# V1_9.net
KiCad netlist of a schematic drawn in Altium Designer
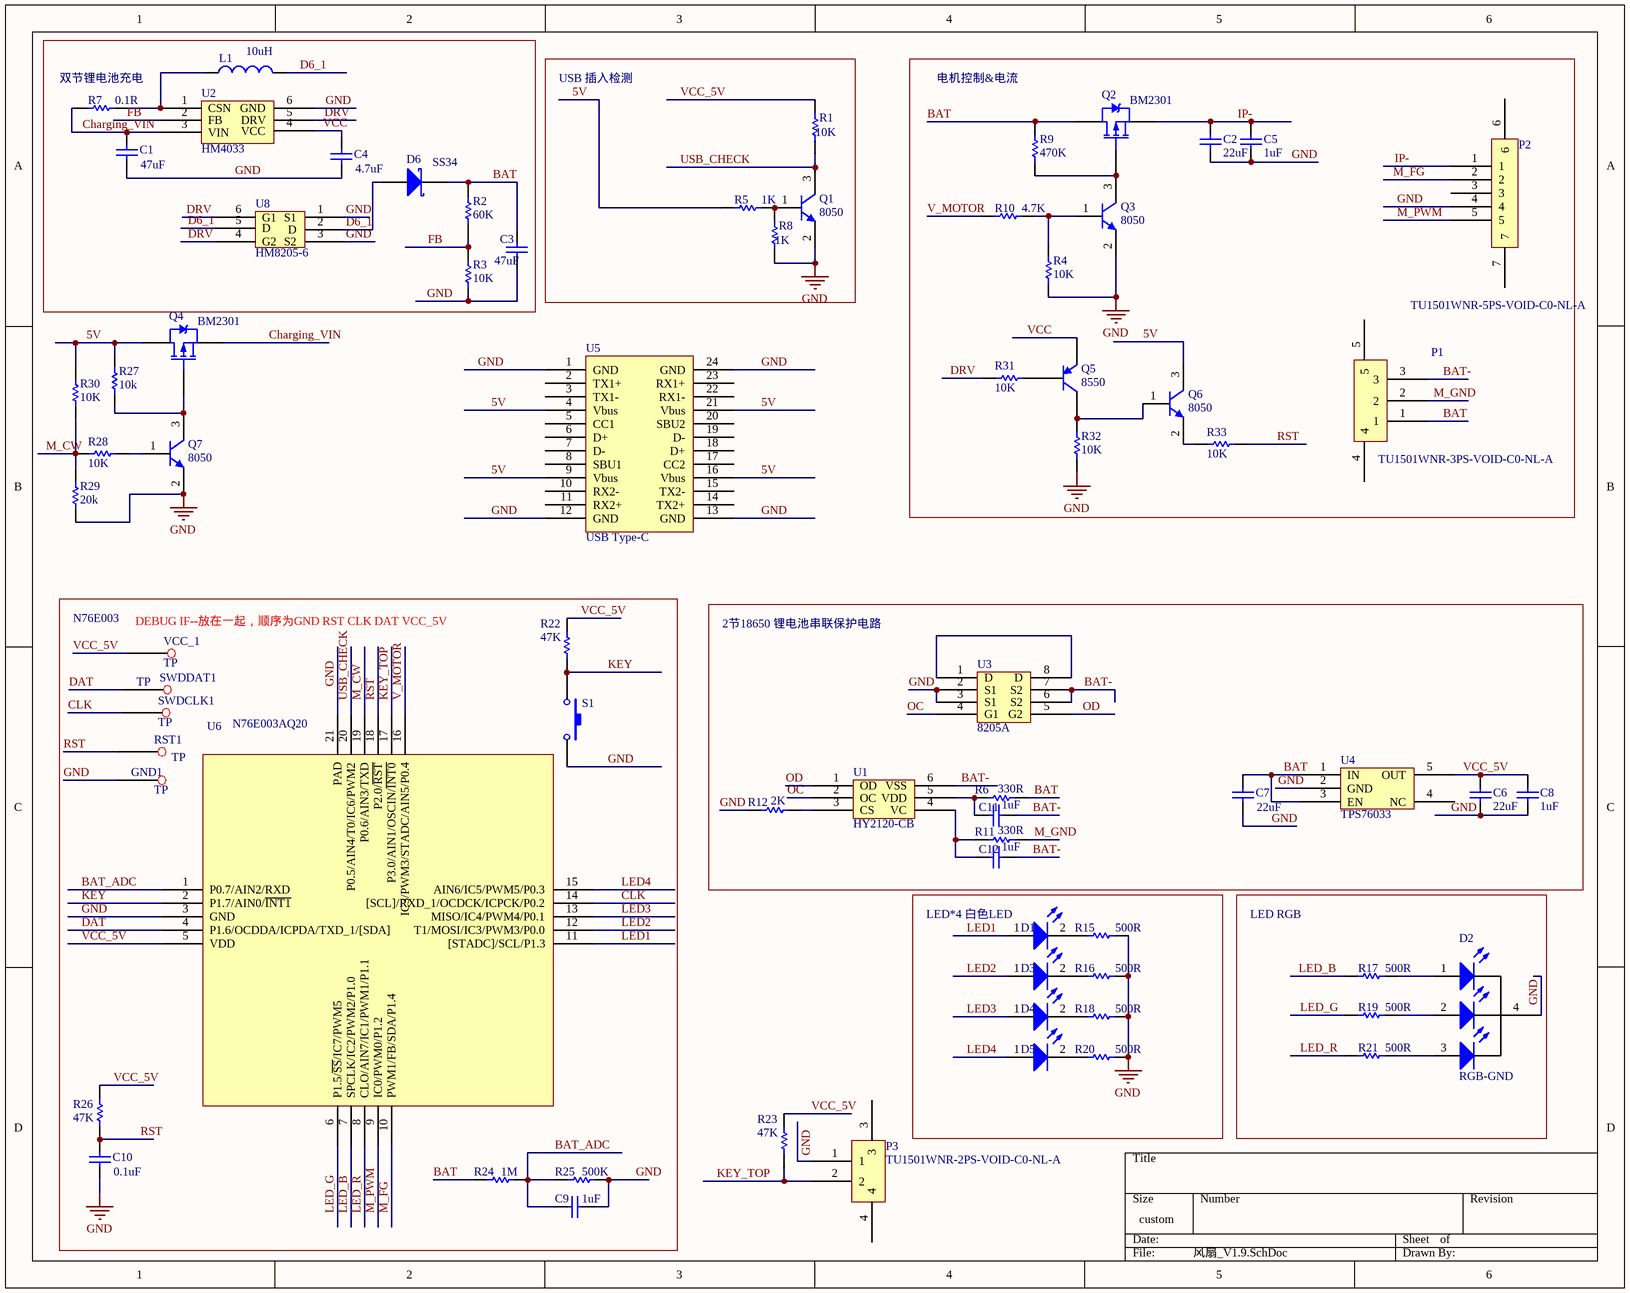
[diagram p0: 风扇_V1.9.SchDoc]

(export (version "E")
  (design (tool "Eeschema 10.0.6"))
  (components
    (comp (ref "C1")
      (value "47uF")
      (footprint "C-0603")
      (description "Capacitor")
      (fields (field (name "PUBLISHER") "Altium Limited"))
      (libsource (lib "Miscellaneous Devices") (part "Cap"))
    )
    (comp (ref "C2")
      (value "22uF")
      (footprint "C-0603")
      (description "Capacitor")
      (fields (field (name "PUBLISHER") "Altium Limited"))
      (libsource (lib "Miscellaneous Devices") (part "Cap"))
    )
    (comp (ref "C3")
      (value "47uF")
      (footprint "C-0603")
      (description "Capacitor")
      (fields (field (name "PUBLISHER") "Altium Limited"))
      (libsource (lib "Miscellaneous Devices") (part "Cap"))
    )
    (comp (ref "C4")
      (value "4.7uF")
      (footprint "C-0402")
      (description "Capacitor")
      (fields (field (name "PUBLISHER") "Altium Limited"))
      (libsource (lib "Miscellaneous Devices") (part "Cap"))
    )
    (comp (ref "C5")
      (value "1uF")
      (footprint "C-0402")
      (description "Capacitor")
      (fields (field (name "PUBLISHER") "Altium Limited"))
      (libsource (lib "Miscellaneous Devices") (part "Cap"))
    )
    (comp (ref "C6")
      (value "22uF")
      (footprint "C-0603")
      (description "Capacitor")
      (fields (field (name "PUBLISHER") "Altium Limited"))
      (libsource (lib "Miscellaneous Devices") (part "Cap"))
    )
    (comp (ref "C7")
      (value "22uF")
      (footprint "C-0603")
      (description "Capacitor")
      (fields (field (name "PUBLISHER") "Altium Limited"))
      (libsource (lib "Miscellaneous Devices") (part "Cap"))
    )
    (comp (ref "C8")
      (value "1uF")
      (footprint "C-0402")
      (description "Capacitor")
      (fields (field (name "PUBLISHER") "Altium Limited"))
      (libsource (lib "Miscellaneous Devices") (part "Cap"))
    )
    (comp (ref "C9")
      (value "1uF")
      (footprint "C-0402")
      (description "Capacitor")
      (fields (field (name "PUBLISHER") "Altium Limited"))
      (libsource (lib "Miscellaneous Devices") (part "Cap"))
    )
    (comp (ref "C10")
      (value "0.1uF")
      (footprint "C-0402")
      (description "Capacitor")
      (fields (field (name "PUBLISHER") "Altium Limited"))
      (libsource (lib "Miscellaneous Devices") (part "Cap"))
    )
    (comp (ref "C11")
      (value "1uF")
      (footprint "C-0402")
      (description "Capacitor")
      (fields (field (name "PUBLISHER") "Altium Limited"))
      (libsource (lib "Miscellaneous Devices") (part "Cap"))
    )
    (comp (ref "C12")
      (value "1uF")
      (footprint "C-0402")
      (description "Capacitor")
      (fields (field (name "PUBLISHER") "Altium Limited"))
      (libsource (lib "Miscellaneous Devices") (part "Cap"))
    )
    (comp (ref "D1")
      (value "LED0")
      (footprint "LED-0603")
      (description "Typical INFRARED GaAs LED")
      (fields (field (name "PUBLISHER") "Altium Limited"))
      (libsource (lib "Miscellaneous Devices") (part "LED0"))
    )
    (comp (ref "D2")
      (value "RGB-GND")
      (footprint "0603*2-LED")
      (libsource (lib "Others_IC_SCH_LIB") (part "RGB-GND"))
    )
    (comp (ref "D3")
      (value "LED0")
      (footprint "LED-0603")
      (description "Typical INFRARED GaAs LED")
      (fields (field (name "PUBLISHER") "Altium Limited"))
      (libsource (lib "Miscellaneous Devices") (part "LED0"))
    )
    (comp (ref "D4")
      (value "LED0")
      (footprint "LED-0603")
      (description "Typical INFRARED GaAs LED")
      (fields (field (name "PUBLISHER") "Altium Limited"))
      (libsource (lib "Miscellaneous Devices") (part "LED0"))
    )
    (comp (ref "D5")
      (value "LED0")
      (footprint "LED-0603")
      (description "Typical INFRARED GaAs LED")
      (fields (field (name "PUBLISHER") "Altium Limited"))
      (libsource (lib "Miscellaneous Devices") (part "LED0"))
    )
    (comp (ref "D6")
      (value "SS34")
      (footprint "HM4033 V1.0:DSMD")
      (description "Schottky Rectifier")
      (fields (field (name "PUBLISHER") "Altium Limited"))
      (libsource (lib "Miscellaneous Devices") (part "Diode 10TQ035"))
    )
    (comp (ref "GND1") (value "TP") (footprint "TP-1.5") (libsource (lib "Others_IC_SCH_LIB") (part "TP")))
    (comp (ref "L1")
      (value "10uH")
      (footprint "L-SMD")
      (description "Inductor")
      (fields (field (name "PUBLISHER") "Altium Limited"))
      (libsource (lib "Miscellaneous Devices") (part "Inductor"))
    )
    (comp (ref "P1")
      (value "TU1501WNR-3PS-VOID-C0-NL-A")
      (footprint "TU1501WNR-3PS-VOID-*-NL-A")
      (libsource (lib "Others_IC_SCH_LIB") (part "TU1501WNR-3PS-VOID-C0-NL-A"))
    )
    (comp (ref "P2")
      (value "TU1501WNR-5PS-VOID-C0-NL-A")
      (footprint "TU1501WNR-5PS-VOID-*-NL-A")
      (libsource (lib "Others_IC_SCH_LIB") (part "TU1501WNR-5PS-VOID-C0-NL-A"))
    )
    (comp (ref "P3")
      (value "TU1501WNR-2PS-VOID-C0-NL-A")
      (footprint "TU1501WNR-2PS-VOID-*-NL-A")
      (libsource (lib "Others_IC_SCH_LIB") (part "TU1501WNR-2PS-VOID-C0-NL-A"))
    )
    (comp (ref "Q1")
      (value "8050")
      (footprint "SOT-23")
      (description "NPN Bipolar Transistor")
      (fields (field (name "PUBLISHER") "Altium Limited"))
      (libsource (lib "Miscellaneous Devices") (part "NPN"))
    )
    (comp (ref "Q2")
      (value "BM2301")
      (footprint "SOT-23")
      (description "P-Channel Power MOSFET")
      (fields (field (name "PUBLISHER") "Altium Limited"))
      (libsource (lib "Miscellaneous Devices") (part "PMOS-2"))
    )
    (comp (ref "Q3")
      (value "8050")
      (footprint "SOT-23")
      (description "NPN Bipolar Transistor")
      (fields (field (name "PUBLISHER") "Altium Limited"))
      (libsource (lib "Miscellaneous Devices") (part "NPN"))
    )
    (comp (ref "Q4")
      (value "BM2301")
      (footprint "SOT-23")
      (description "P-Channel Power MOSFET")
      (fields (field (name "PUBLISHER") "Altium Limited"))
      (libsource (lib "Miscellaneous Devices") (part "PMOS-2"))
    )
    (comp (ref "Q5")
      (value "8550")
      (footprint "SOT-23")
      (description "PNP Bipolar Transistor")
      (fields (field (name "PUBLISHER") "Altium Limited"))
      (libsource (lib "Miscellaneous Devices") (part "PNP"))
    )
    (comp (ref "Q6")
      (value "8050")
      (footprint "SOT-23")
      (description "NPN Bipolar Transistor")
      (fields (field (name "PUBLISHER") "Altium Limited"))
      (libsource (lib "Miscellaneous Devices") (part "NPN"))
    )
    (comp (ref "Q7")
      (value "8050")
      (footprint "SOT-23")
      (description "NPN Bipolar Transistor")
      (fields (field (name "PUBLISHER") "Altium Limited"))
      (libsource (lib "Miscellaneous Devices") (part "NPN"))
    )
    (comp (ref "R1")
      (value "10K")
      (footprint "R-0402")
      (description "Resistor")
      (fields (field (name "PUBLISHER") "Altium Limited"))
      (libsource (lib "Miscellaneous Devices") (part "Res1"))
    )
    (comp (ref "R2")
      (value "60K")
      (footprint "R-0402")
      (description "Resistor")
      (fields (field (name "PUBLISHER") "Altium Limited"))
      (libsource (lib "Miscellaneous Devices") (part "Res1"))
    )
    (comp (ref "R3")
      (value "10K")
      (footprint "R-0402")
      (description "Resistor")
      (fields (field (name "PUBLISHER") "Altium Limited"))
      (libsource (lib "Miscellaneous Devices") (part "Res1"))
    )
    (comp (ref "R4")
      (value "10K")
      (footprint "R-0402")
      (description "Resistor")
      (fields (field (name "PUBLISHER") "Altium Limited"))
      (libsource (lib "Miscellaneous Devices") (part "Res1"))
    )
    (comp (ref "R5")
      (value "1K")
      (footprint "R-0402")
      (description "Resistor")
      (fields (field (name "PUBLISHER") "Altium Limited"))
      (libsource (lib "Miscellaneous Devices") (part "Res1"))
    )
    (comp (ref "R6")
      (value "330R")
      (footprint "R-0402")
      (description "Resistor")
      (fields (field (name "PUBLISHER") "Altium Limited"))
      (libsource (lib "Miscellaneous Devices") (part "Res1"))
    )
    (comp (ref "R7")
      (value "0.1R")
      (footprint "R-0402")
      (description "Resistor")
      (fields (field (name "PUBLISHER") "Altium Limited"))
      (libsource (lib "Miscellaneous Devices") (part "Res1"))
    )
    (comp (ref "R8")
      (value "1K")
      (footprint "R-0402")
      (description "Resistor")
      (fields (field (name "PUBLISHER") "Altium Limited"))
      (libsource (lib "Miscellaneous Devices") (part "Res1"))
    )
    (comp (ref "R9")
      (value "470K")
      (footprint "R-0402")
      (description "Resistor")
      (fields (field (name "PUBLISHER") "Altium Limited"))
      (libsource (lib "Miscellaneous Devices") (part "Res1"))
    )
    (comp (ref "R10")
      (value "4.7K")
      (footprint "R-0402")
      (description "Resistor")
      (fields (field (name "PUBLISHER") "Altium Limited"))
      (libsource (lib "Miscellaneous Devices") (part "Res1"))
    )
    (comp (ref "R11")
      (value "330R")
      (footprint "R-0402")
      (description "Resistor")
      (fields (field (name "PUBLISHER") "Altium Limited"))
      (libsource (lib "Miscellaneous Devices") (part "Res1"))
    )
    (comp (ref "R12")
      (value "2K")
      (footprint "R-0402")
      (description "Resistor")
      (fields (field (name "PUBLISHER") "Altium Limited"))
      (libsource (lib "Miscellaneous Devices") (part "Res1"))
    )
    (comp (ref "R15")
      (value "500R")
      (footprint "R-0402")
      (description "Resistor")
      (fields (field (name "PUBLISHER") "Altium Limited"))
      (libsource (lib "Miscellaneous Devices") (part "Res1"))
    )
    (comp (ref "R16")
      (value "500R")
      (footprint "R-0402")
      (description "Resistor")
      (fields (field (name "PUBLISHER") "Altium Limited"))
      (libsource (lib "Miscellaneous Devices") (part "Res1"))
    )
    (comp (ref "R17")
      (value "500R")
      (footprint "R-0402")
      (description "Resistor")
      (fields (field (name "PUBLISHER") "Altium Limited"))
      (libsource (lib "Miscellaneous Devices") (part "Res1"))
    )
    (comp (ref "R18")
      (value "500R")
      (footprint "R-0402")
      (description "Resistor")
      (fields (field (name "PUBLISHER") "Altium Limited"))
      (libsource (lib "Miscellaneous Devices") (part "Res1"))
    )
    (comp (ref "R19")
      (value "500R")
      (footprint "R-0402")
      (description "Resistor")
      (fields (field (name "PUBLISHER") "Altium Limited"))
      (libsource (lib "Miscellaneous Devices") (part "Res1"))
    )
    (comp (ref "R20")
      (value "500R")
      (footprint "R-0402")
      (description "Resistor")
      (fields (field (name "PUBLISHER") "Altium Limited"))
      (libsource (lib "Miscellaneous Devices") (part "Res1"))
    )
    (comp (ref "R21")
      (value "500R")
      (footprint "R-0402")
      (description "Resistor")
      (fields (field (name "PUBLISHER") "Altium Limited"))
      (libsource (lib "Miscellaneous Devices") (part "Res1"))
    )
    (comp (ref "R22")
      (value "47K")
      (footprint "R-0402")
      (description "Resistor")
      (fields (field (name "PUBLISHER") "Altium Limited"))
      (libsource (lib "Miscellaneous Devices") (part "Res1"))
    )
    (comp (ref "R23")
      (value "47K")
      (footprint "R-0402")
      (description "Resistor")
      (fields (field (name "PUBLISHER") "Altium Limited"))
      (libsource (lib "Miscellaneous Devices") (part "Res1"))
    )
    (comp (ref "R24")
      (value "1M")
      (footprint "R-0402")
      (description "Resistor")
      (fields (field (name "PUBLISHER") "Altium Limited"))
      (libsource (lib "Miscellaneous Devices") (part "Res1"))
    )
    (comp (ref "R25")
      (value "500K")
      (footprint "R-0402")
      (description "Resistor")
      (fields (field (name "PUBLISHER") "Altium Limited"))
      (libsource (lib "Miscellaneous Devices") (part "Res1"))
    )
    (comp (ref "R26")
      (value "47K")
      (footprint "R-0402")
      (description "Resistor")
      (fields (field (name "PUBLISHER") "Altium Limited"))
      (libsource (lib "Miscellaneous Devices") (part "Res1"))
    )
    (comp (ref "R27")
      (value "10k")
      (footprint "R-0402")
      (description "Resistor")
      (fields (field (name "PUBLISHER") "Altium Limited"))
      (libsource (lib "Miscellaneous Devices") (part "Res1"))
    )
    (comp (ref "R28")
      (value "10K")
      (footprint "R-0402")
      (description "Resistor")
      (fields (field (name "PUBLISHER") "Altium Limited"))
      (libsource (lib "Miscellaneous Devices") (part "Res1"))
    )
    (comp (ref "R29")
      (value "20k")
      (footprint "R-0402")
      (description "Resistor")
      (fields (field (name "PUBLISHER") "Altium Limited"))
      (libsource (lib "Miscellaneous Devices") (part "Res1"))
    )
    (comp (ref "R30")
      (value "10K")
      (footprint "R-0402")
      (description "Resistor")
      (fields (field (name "PUBLISHER") "Altium Limited"))
      (libsource (lib "Miscellaneous Devices") (part "Res1"))
    )
    (comp (ref "R31")
      (value "10K")
      (footprint "R-0402")
      (description "Resistor")
      (fields (field (name "PUBLISHER") "Altium Limited"))
      (libsource (lib "Miscellaneous Devices") (part "Res1"))
    )
    (comp (ref "R32")
      (value "10K")
      (footprint "R-0402")
      (description "Resistor")
      (fields (field (name "PUBLISHER") "Altium Limited"))
      (libsource (lib "Miscellaneous Devices") (part "Res1"))
    )
    (comp (ref "R33")
      (value "10K")
      (footprint "R-0402")
      (description "Resistor")
      (fields (field (name "PUBLISHER") "Altium Limited"))
      (libsource (lib "Miscellaneous Devices") (part "Res1"))
    )
    (comp (ref "RST1") (value "TP") (footprint "TP-1.5") (libsource (lib "Others_IC_SCH_LIB") (part "TP")))
    (comp (ref "S1")
      (value "SW-PB")
      (footprint "SWITCH-4P-SMT")
      (description "Switch")
      (fields (field (name "PUBLISHER") "Altium Limited"))
      (libsource (lib "Miscellaneous Devices") (part "SW-PB"))
    )
    (comp (ref "SWDCLK1") (value "TP") (footprint "TP-1.5") (libsource (lib "Others_IC_SCH_LIB") (part "TP")))
    (comp (ref "SWDDAT1") (value "TP") (footprint "TP-1.5") (libsource (lib "Others_IC_SCH_LIB") (part "TP")))
    (comp (ref "U1")
      (value "HY2120-CB")
      (footprint "SOT-23-6L")
      (libsource (lib "Others_IC_SCH_LIB") (part "HY2120"))
    )
    (comp (ref "U2")
      (value "HM4033")
      (footprint "SOT-23-6L")
      (libsource (lib "Others_IC_SCH_LIB") (part "HM4033"))
    )
    (comp (ref "U3")
      (value "8205A")
      (footprint "TSSOP8")
      (libsource (lib "Others_IC_SCH_LIB") (part "8205A"))
    )
    (comp (ref "U4")
      (value "TPS76033")
      (footprint "SOT-23-5")
      (libsource (lib "Others_IC_SCH_LIB") (part "TPS76033"))
    )
    (comp (ref "U5")
      (value "USB Type-C")
      (footprint "USB-type C")
      (libsource (lib "Others_IC_SCH_LIB") (part "USB Type-C"))
    )
    (comp (ref "U6")
      (value "N76E003AQ20")
      (footprint "QFN-20 0.4mm")
      (libsource (lib "Others_IC_SCH_LIB") (part "N76E003AQ20"))
    )
    (comp (ref "U8")
      (value "HM8205-6")
      (footprint "SOT-23-6L")
      (libsource (lib "Others_IC_SCH_LIB") (part "HM8205-6"))
    )
    (comp (ref "VCC_1") (value "TP") (footprint "TP-1.5") (libsource (lib "Others_IC_SCH_LIB") (part "TP")))
  )
  (nets
    (net (code "1") (name "/5V") (class "Default")
      (node (ref "Q4") (pin "2") (pinfunction "D_2") (pintype "passive"))
      (node (ref "Q6") (pin "3") (pinfunction "C_3") (pintype "passive"))
      (node (ref "R27") (pin "2") (pinfunction "2_2") (pintype "passive"))
      (node (ref "R30") (pin "1") (pinfunction "1_1") (pintype "passive"))
      (node (ref "R5") (pin "1") (pinfunction "1_1") (pintype "passive"))
      (node (ref "U5") (pin "16") (pinfunction "Vbus_16") (pintype "passive"))
      (node (ref "U5") (pin "21") (pinfunction "Vbus_21") (pintype "passive"))
      (node (ref "U5") (pin "4") (pinfunction "Vbus_4") (pintype "passive"))
      (node (ref "U5") (pin "9") (pinfunction "Vbus_9") (pintype "passive"))
    )
    (net (code "2") (name "/BAT") (class "Default")
      (node (ref "C3") (pin "2") (pinfunction "2_2") (pintype "passive"))
      (node (ref "C7") (pin "2") (pinfunction "2_2") (pintype "passive"))
      (node (ref "D6") (pin "1") (pinfunction "K_1") (pintype "passive"))
      (node (ref "P1") (pin "1") (pinfunction "1_1") (pintype "passive"))
      (node (ref "Q2") (pin "2") (pinfunction "D_2") (pintype "passive"))
      (node (ref "R2") (pin "1") (pinfunction "1_1") (pintype "passive"))
      (node (ref "R24") (pin "1") (pinfunction "1_1") (pintype "passive"))
      (node (ref "R6") (pin "2") (pinfunction "2_2") (pintype "passive"))
      (node (ref "R9") (pin "2") (pinfunction "2_2") (pintype "passive"))
      (node (ref "U4") (pin "1") (pinfunction "IN_1") (pintype "passive"))
      (node (ref "U4") (pin "3") (pinfunction "EN_3") (pintype "passive"))
    )
    (net (code "3") (name "/BAT-") (class "Default")
      (node (ref "C11") (pin "1") (pinfunction "1_1") (pintype "passive"))
      (node (ref "C12") (pin "1") (pinfunction "1_1") (pintype "passive"))
      (node (ref "P1") (pin "3") (pinfunction "3_3") (pintype "passive"))
      (node (ref "U1") (pin "6") (pinfunction "VSS_6") (pintype "passive"))
      (node (ref "U3") (pin "6") (pinfunction "S2_6") (pintype "passive"))
      (node (ref "U3") (pin "7") (pinfunction "S2_7") (pintype "passive"))
    )
    (net (code "4") (name "/BAT_ADC") (class "Default")
      (node (ref "C9") (pin "2") (pinfunction "2_2") (pintype "passive"))
      (node (ref "R24") (pin "2") (pinfunction "2_2") (pintype "passive"))
      (node (ref "R25") (pin "1") (pinfunction "1_1") (pintype "passive"))
      (node (ref "U6") (pin "1") (pinfunction "P0.7/AIN2/RXD_1") (pintype "passive"))
    )
    (net (code "5") (name "/CLK") (class "Default")
      (node (ref "SWDCLK1") (pin "1") (pinfunction "1_1") (pintype "passive"))
      (node (ref "U6") (pin "14") (pinfunction "[SCL]/RXD_1/OCDCK/ICPCK/P0.2_14") (pintype "passive"))
    )
    (net (code "6") (name "/Charging_VIN") (class "Default")
      (node (ref "C1") (pin "1") (pinfunction "1_1") (pintype "passive"))
      (node (ref "Q4") (pin "3") (pinfunction "S_3") (pintype "passive"))
      (node (ref "R7") (pin "2") (pinfunction "2_2") (pintype "passive"))
      (node (ref "U2") (pin "3") (pinfunction "VIN_3") (pintype "passive"))
    )
    (net (code "7") (name "/D6_1") (class "Default")
      (node (ref "D6") (pin "3") (pinfunction "A_3") (pintype "passive"))
      (node (ref "L1") (pin "2") (pinfunction "2_2") (pintype "passive"))
      (node (ref "U8") (pin "2") (pinfunction "D_2") (pintype "passive"))
      (node (ref "U8") (pin "5") (pinfunction "D_5") (pintype "passive"))
    )
    (net (code "8") (name "/DAT") (class "Default")
      (node (ref "SWDDAT1") (pin "1") (pinfunction "1_1") (pintype "passive"))
      (node (ref "U6") (pin "4") (pinfunction "P1.6/OCDDA/ICPDA/TXD_1/[SDA]_4") (pintype "passive"))
    )
    (net (code "9") (name "/DRV") (class "Default")
      (node (ref "R31") (pin "1") (pinfunction "1_1") (pintype "passive"))
      (node (ref "U2") (pin "5") (pinfunction "DRV_5") (pintype "passive"))
      (node (ref "U8") (pin "4") (pinfunction "G2_4") (pintype "passive"))
      (node (ref "U8") (pin "6") (pinfunction "G1_6") (pintype "passive"))
    )
    (net (code "10") (name "/FB") (class "Default")
      (node (ref "R2") (pin "2") (pinfunction "2_2") (pintype "passive"))
      (node (ref "R3") (pin "1") (pinfunction "1_1") (pintype "passive"))
      (node (ref "U2") (pin "2") (pinfunction "FB_2") (pintype "passive"))
    )
    (net (code "11") (name "/IP-") (class "Default")
      (node (ref "C2") (pin "2") (pinfunction "2_2") (pintype "passive"))
      (node (ref "C5") (pin "2") (pinfunction "2_2") (pintype "passive"))
      (node (ref "P2") (pin "1") (pinfunction "1_1") (pintype "passive"))
      (node (ref "Q2") (pin "3") (pinfunction "S_3") (pintype "passive"))
    )
    (net (code "12") (name "/KEY") (class "Default")
      (node (ref "R22") (pin "1") (pinfunction "1_1") (pintype "passive"))
      (node (ref "S1") (pin "1") (pinfunction "1_1") (pintype "passive"))
      (node (ref "U6") (pin "2") (pinfunction "P1.7/AIN0/~{INT1}_2") (pintype "passive"))
    )
    (net (code "13") (name "/KEY_TOP") (class "Default")
      (node (ref "P3") (pin "2") (pinfunction "2_2") (pintype "passive"))
      (node (ref "R23") (pin "1") (pinfunction "1_1") (pintype "passive"))
      (node (ref "U6") (pin "17") (pinfunction "P3.0/AIN1/OSCIN/~{INT0}_17") (pintype "passive"))
    )
    (net (code "14") (name "/LED1") (class "Default")
      (node (ref "D1") (pin "1") (pinfunction "A_1") (pintype "passive"))
      (node (ref "U6") (pin "11") (pinfunction "[STADC]/SCL/P1.3_11") (pintype "passive"))
    )
    (net (code "15") (name "/LED2") (class "Default")
      (node (ref "D3") (pin "1") (pinfunction "A_1") (pintype "passive"))
      (node (ref "U6") (pin "12") (pinfunction "T1/MOSI/IC3/PWM3/P0.0_12") (pintype "passive"))
    )
    (net (code "16") (name "/LED3") (class "Default")
      (node (ref "D4") (pin "1") (pinfunction "A_1") (pintype "passive"))
      (node (ref "U6") (pin "13") (pinfunction "MISO/IC4/PWM4/P0.1_13") (pintype "passive"))
    )
    (net (code "17") (name "/LED4") (class "Default")
      (node (ref "D5") (pin "1") (pinfunction "A_1") (pintype "passive"))
      (node (ref "U6") (pin "15") (pinfunction "AIN6/IC5/PWM5/P0.3_15") (pintype "passive"))
    )
    (net (code "18") (name "/LED_B") (class "Default")
      (node (ref "R17") (pin "1") (pinfunction "1_1") (pintype "passive"))
      (node (ref "U6") (pin "7") (pinfunction "SPCLK/IC2/PWM2/P1.0_7") (pintype "passive"))
    )
    (net (code "19") (name "/LED_G") (class "Default")
      (node (ref "R19") (pin "1") (pinfunction "1_1") (pintype "passive"))
      (node (ref "U6") (pin "6") (pinfunction "P1.5/~{SS}/IC7/PWM5_6") (pintype "passive"))
    )
    (net (code "20") (name "/LED_R") (class "Default")
      (node (ref "R21") (pin "1") (pinfunction "1_1") (pintype "passive"))
      (node (ref "U6") (pin "8") (pinfunction "CLO/AIN7/IC1/PWM1/P1.1_8") (pintype "passive"))
    )
    (net (code "21") (name "/M_CW") (class "Default")
      (node (ref "R28") (pin "2") (pinfunction "2_2") (pintype "passive"))
      (node (ref "R29") (pin "1") (pinfunction "1_1") (pintype "passive"))
      (node (ref "R30") (pin "2") (pinfunction "2_2") (pintype "passive"))
      (node (ref "U6") (pin "19") (pinfunction "P0.6/AIN3/TXD_19") (pintype "passive"))
    )
    (net (code "22") (name "/M_FG") (class "Default")
      (node (ref "P2") (pin "2") (pinfunction "2_2") (pintype "passive"))
      (node (ref "U6") (pin "10") (pinfunction "PWM1/FB/SDA/P1.4_10") (pintype "passive"))
    )
    (net (code "23") (name "/M_GND") (class "Default")
      (node (ref "P1") (pin "2") (pinfunction "2_2") (pintype "passive"))
      (node (ref "R11") (pin "2") (pinfunction "2_2") (pintype "passive"))
    )
    (net (code "24") (name "/M_PWM") (class "Default")
      (node (ref "P2") (pin "5") (pinfunction "5_5") (pintype "passive"))
      (node (ref "U6") (pin "9") (pinfunction "IC0/PWM0/P1.2_9") (pintype "passive"))
    )
    (net (code "25") (name "/OC") (class "Default")
      (node (ref "U1") (pin "2") (pinfunction "OC_2") (pintype "passive"))
      (node (ref "U3") (pin "4") (pinfunction "G1_4") (pintype "passive"))
    )
    (net (code "26") (name "/OD") (class "Default")
      (node (ref "U1") (pin "1") (pinfunction "OD_1") (pintype "passive"))
      (node (ref "U3") (pin "5") (pinfunction "G2_5") (pintype "passive"))
    )
    (net (code "27") (name "/RST") (class "Default")
      (node (ref "C10") (pin "2") (pinfunction "2_2") (pintype "passive"))
      (node (ref "R26") (pin "1") (pinfunction "1_1") (pintype "passive"))
      (node (ref "R33") (pin "1") (pinfunction "1_1") (pintype "passive"))
      (node (ref "RST1") (pin "1") (pinfunction "1_1") (pintype "passive"))
      (node (ref "U6") (pin "18") (pinfunction "P2.0/~{RST}_18") (pintype "passive"))
    )
    (net (code "28") (name "/USB_CHECK") (class "Default")
      (node (ref "Q1") (pin "3") (pinfunction "C_3") (pintype "passive"))
      (node (ref "R1") (pin "1") (pinfunction "1_1") (pintype "passive"))
      (node (ref "U6") (pin "20") (pinfunction "P0.5/AIN4/T0/IC6/PWM2_20") (pintype "passive"))
    )
    (net (code "29") (name "/VCC") (class "Default")
      (node (ref "C4") (pin "1") (pinfunction "1_1") (pintype "passive"))
      (node (ref "Q5") (pin "3") (pinfunction "E_3") (pintype "passive"))
      (node (ref "U2") (pin "4") (pinfunction "VCC_4") (pintype "passive"))
    )
    (net (code "30") (name "/VCC_5V") (class "Default")
      (node (ref "C6") (pin "2") (pinfunction "2_2") (pintype "passive"))
      (node (ref "C8") (pin "2") (pinfunction "2_2") (pintype "passive"))
      (node (ref "R1") (pin "2") (pinfunction "2_2") (pintype "passive"))
      (node (ref "R22") (pin "2") (pinfunction "2_2") (pintype "passive"))
      (node (ref "R23") (pin "2") (pinfunction "2_2") (pintype "passive"))
      (node (ref "R26") (pin "2") (pinfunction "2_2") (pintype "passive"))
      (node (ref "U4") (pin "5") (pinfunction "OUT_5") (pintype "passive"))
      (node (ref "U6") (pin "5") (pinfunction "VDD_5") (pintype "passive"))
      (node (ref "VCC_1") (pin "1") (pinfunction "1_1") (pintype "passive"))
    )
    (net (code "31") (name "/V_MOTOR") (class "Default")
      (node (ref "R10") (pin "1") (pinfunction "1_1") (pintype "passive"))
      (node (ref "U6") (pin "16") (pinfunction "IC3/PWM3/STADC/AIN5/P0.4_16") (pintype "passive"))
    )
    (net (code "32") (name "GND") (class "Default")
      (node (ref "C1") (pin "2") (pinfunction "2_2") (pintype "passive"))
      (node (ref "C10") (pin "1") (pinfunction "1_1") (pintype "passive"))
      (node (ref "C2") (pin "1") (pinfunction "1_1") (pintype "passive"))
      (node (ref "C3") (pin "1") (pinfunction "1_1") (pintype "passive"))
      (node (ref "C4") (pin "2") (pinfunction "2_2") (pintype "passive"))
      (node (ref "C5") (pin "1") (pinfunction "1_1") (pintype "passive"))
      (node (ref "C6") (pin "1") (pinfunction "1_1") (pintype "passive"))
      (node (ref "C7") (pin "1") (pinfunction "1_1") (pintype "passive"))
      (node (ref "C8") (pin "1") (pinfunction "1_1") (pintype "passive"))
      (node (ref "C9") (pin "1") (pinfunction "1_1") (pintype "passive"))
      (node (ref "D2") (pin "4") (pinfunction "4_4") (pintype "passive"))
      (node (ref "GND1") (pin "1") (pinfunction "1_1") (pintype "passive"))
      (node (ref "P2") (pin "4") (pinfunction "4_4") (pintype "passive"))
      (node (ref "P3") (pin "1") (pinfunction "1_1") (pintype "passive"))
      (node (ref "Q1") (pin "2") (pinfunction "E_2") (pintype "passive"))
      (node (ref "Q3") (pin "2") (pinfunction "E_2") (pintype "passive"))
      (node (ref "Q7") (pin "2") (pinfunction "E_2") (pintype "passive"))
      (node (ref "R12") (pin "1") (pinfunction "1_1") (pintype "passive"))
      (node (ref "R15") (pin "2") (pinfunction "2_2") (pintype "passive"))
      (node (ref "R16") (pin "2") (pinfunction "2_2") (pintype "passive"))
      (node (ref "R18") (pin "2") (pinfunction "2_2") (pintype "passive"))
      (node (ref "R20") (pin "2") (pinfunction "2_2") (pintype "passive"))
      (node (ref "R25") (pin "2") (pinfunction "2_2") (pintype "passive"))
      (node (ref "R29") (pin "2") (pinfunction "2_2") (pintype "passive"))
      (node (ref "R3") (pin "2") (pinfunction "2_2") (pintype "passive"))
      (node (ref "R32") (pin "1") (pinfunction "1_1") (pintype "passive"))
      (node (ref "R4") (pin "1") (pinfunction "1_1") (pintype "passive"))
      (node (ref "R8") (pin "2") (pinfunction "2_2") (pintype "passive"))
      (node (ref "S1") (pin "2") (pinfunction "2_2") (pintype "passive"))
      (node (ref "U2") (pin "6") (pinfunction "GND_6") (pintype "passive"))
      (node (ref "U3") (pin "2") (pinfunction "S1_2") (pintype "passive"))
      (node (ref "U3") (pin "3") (pinfunction "S1_3") (pintype "passive"))
      (node (ref "U4") (pin "2") (pinfunction "GND_2") (pintype "passive"))
      (node (ref "U5") (pin "1") (pinfunction "GND_1") (pintype "passive"))
      (node (ref "U5") (pin "12") (pinfunction "GND_12") (pintype "passive"))
      (node (ref "U5") (pin "13") (pinfunction "GND_13") (pintype "passive"))
      (node (ref "U5") (pin "24") (pinfunction "GND_24") (pintype "passive"))
      (node (ref "U6") (pin "21") (pinfunction "PAD_21") (pintype "passive"))
      (node (ref "U6") (pin "3") (pinfunction "GND_3") (pintype "passive"))
      (node (ref "U8") (pin "1") (pinfunction "S1_1") (pintype "passive"))
      (node (ref "U8") (pin "3") (pinfunction "S2_3") (pintype "passive"))
    )
    (net (code "33") (name "Net-(D1-K)") (class "Default")
      (node (ref "D1") (pin "2") (pinfunction "K_2") (pintype "passive"))
      (node (ref "R15") (pin "1") (pinfunction "1_1") (pintype "passive"))
    )
    (net (code "34") (name "Net-(D2-Pad1)") (class "Default")
      (node (ref "D2") (pin "1") (pinfunction "1_1") (pintype "passive"))
      (node (ref "R17") (pin "2") (pinfunction "2_2") (pintype "passive"))
    )
    (net (code "35") (name "Net-(D2-Pad2)") (class "Default")
      (node (ref "D2") (pin "2") (pinfunction "2_2") (pintype "passive"))
      (node (ref "R19") (pin "2") (pinfunction "2_2") (pintype "passive"))
    )
    (net (code "36") (name "Net-(D2-Pad3)") (class "Default")
      (node (ref "D2") (pin "3") (pinfunction "3_3") (pintype "passive"))
      (node (ref "R21") (pin "2") (pinfunction "2_2") (pintype "passive"))
    )
    (net (code "37") (name "Net-(D3-K)") (class "Default")
      (node (ref "D3") (pin "2") (pinfunction "K_2") (pintype "passive"))
      (node (ref "R16") (pin "1") (pinfunction "1_1") (pintype "passive"))
    )
    (net (code "38") (name "Net-(D4-K)") (class "Default")
      (node (ref "D4") (pin "2") (pinfunction "K_2") (pintype "passive"))
      (node (ref "R18") (pin "1") (pinfunction "1_1") (pintype "passive"))
    )
    (net (code "39") (name "Net-(D5-K)") (class "Default")
      (node (ref "D5") (pin "2") (pinfunction "K_2") (pintype "passive"))
      (node (ref "R20") (pin "1") (pinfunction "1_1") (pintype "passive"))
    )
    (net (code "40") (name "Net-(Q1-B)") (class "Default")
      (node (ref "Q1") (pin "1") (pinfunction "B_1") (pintype "passive"))
      (node (ref "R5") (pin "2") (pinfunction "2_2") (pintype "passive"))
      (node (ref "R8") (pin "1") (pinfunction "1_1") (pintype "passive"))
    )
    (net (code "41") (name "Net-(Q2-G)") (class "Default")
      (node (ref "Q2") (pin "1") (pinfunction "G_1") (pintype "passive"))
      (node (ref "Q3") (pin "3") (pinfunction "C_3") (pintype "passive"))
      (node (ref "R9") (pin "1") (pinfunction "1_1") (pintype "passive"))
    )
    (net (code "42") (name "Net-(Q3-B)") (class "Default")
      (node (ref "Q3") (pin "1") (pinfunction "B_1") (pintype "passive"))
      (node (ref "R10") (pin "2") (pinfunction "2_2") (pintype "passive"))
      (node (ref "R4") (pin "2") (pinfunction "2_2") (pintype "passive"))
    )
    (net (code "43") (name "Net-(Q4-G)") (class "Default")
      (node (ref "Q4") (pin "1") (pinfunction "G_1") (pintype "passive"))
      (node (ref "Q7") (pin "3") (pinfunction "C_3") (pintype "passive"))
      (node (ref "R27") (pin "1") (pinfunction "1_1") (pintype "passive"))
    )
    (net (code "44") (name "Net-(Q5-B)") (class "Default")
      (node (ref "Q5") (pin "2") (pinfunction "B_2") (pintype "passive"))
      (node (ref "R31") (pin "2") (pinfunction "2_2") (pintype "passive"))
    )
    (net (code "45") (name "Net-(Q5-C)") (class "Default")
      (node (ref "Q5") (pin "1") (pinfunction "C_1") (pintype "passive"))
      (node (ref "Q6") (pin "1") (pinfunction "B_1") (pintype "passive"))
      (node (ref "R32") (pin "2") (pinfunction "2_2") (pintype "passive"))
    )
    (net (code "46") (name "Net-(Q6-E)") (class "Default")
      (node (ref "Q6") (pin "2") (pinfunction "E_2") (pintype "passive"))
      (node (ref "R33") (pin "2") (pinfunction "2_2") (pintype "passive"))
    )
    (net (code "47") (name "Net-(Q7-B)") (class "Default")
      (node (ref "Q7") (pin "1") (pinfunction "B_1") (pintype "passive"))
      (node (ref "R28") (pin "1") (pinfunction "1_1") (pintype "passive"))
    )
    (net (code "48") (name "Net-(U1-CS)") (class "Default")
      (node (ref "R12") (pin "2") (pinfunction "2_2") (pintype "passive"))
      (node (ref "U1") (pin "3") (pinfunction "CS_3") (pintype "passive"))
    )
    (net (code "49") (name "Net-(U1-VC)") (class "Default")
      (node (ref "C12") (pin "2") (pinfunction "2_2") (pintype "passive"))
      (node (ref "R11") (pin "1") (pinfunction "1_1") (pintype "passive"))
      (node (ref "U1") (pin "4") (pinfunction "VC_4") (pintype "passive"))
    )
    (net (code "50") (name "Net-(U1-VDD)") (class "Default")
      (node (ref "C11") (pin "2") (pinfunction "2_2") (pintype "passive"))
      (node (ref "R6") (pin "1") (pinfunction "1_1") (pintype "passive"))
      (node (ref "U1") (pin "5") (pinfunction "VDD_5") (pintype "passive"))
    )
    (net (code "51") (name "Net-(U2-CSN)") (class "Default")
      (node (ref "L1") (pin "1") (pinfunction "1_1") (pintype "passive"))
      (node (ref "R7") (pin "1") (pinfunction "1_1") (pintype "passive"))
      (node (ref "U2") (pin "1") (pinfunction "CSN_1") (pintype "passive"))
    )
    (net (code "52") (name "Net-(U3-D-Pad1)") (class "Default")
      (node (ref "U3") (pin "1") (pinfunction "D_1") (pintype "passive"))
      (node (ref "U3") (pin "8") (pinfunction "D_8") (pintype "passive"))
    )
    (net (code "53") (name "unconnected-(P1-Pad4)") (class "Default")
      (node (ref "P1") (pin "4") (pinfunction "4_4") (pintype "passive"))
    )
    (net (code "54") (name "unconnected-(P1-Pad5)") (class "Default")
      (node (ref "P1") (pin "5") (pinfunction "5_5") (pintype "passive"))
    )
    (net (code "55") (name "unconnected-(P2-Pad3)") (class "Default")
      (node (ref "P2") (pin "3") (pinfunction "3_3") (pintype "passive"))
    )
    (net (code "56") (name "unconnected-(P2-Pad6)") (class "Default")
      (node (ref "P2") (pin "6") (pinfunction "6_6") (pintype "passive"))
    )
    (net (code "57") (name "unconnected-(P2-Pad7)") (class "Default")
      (node (ref "P2") (pin "7") (pinfunction "7_7") (pintype "passive"))
    )
    (net (code "58") (name "unconnected-(P3-Pad3)") (class "Default")
      (node (ref "P3") (pin "3") (pinfunction "3_3") (pintype "passive"))
    )
    (net (code "59") (name "unconnected-(P3-Pad4)") (class "Default")
      (node (ref "P3") (pin "4") (pinfunction "4_4") (pintype "passive"))
    )
    (net (code "60") (name "unconnected-(U4-NC-Pad4)") (class "Default")
      (node (ref "U4") (pin "4") (pinfunction "NC_4") (pintype "passive"))
    )
    (net (code "61") (name "unconnected-(U5-CC1-Pad5)") (class "Default")
      (node (ref "U5") (pin "5") (pinfunction "CC1_5") (pintype "passive"))
    )
    (net (code "62") (name "unconnected-(U5-CC2-Pad17)") (class "Default")
      (node (ref "U5") (pin "17") (pinfunction "CC2_17") (pintype "passive"))
    )
    (net (code "63") (name "unconnected-(U5-D+-Pad6)") (class "Default")
      (node (ref "U5") (pin "6") (pinfunction "D+_6") (pintype "passive"))
    )
    (net (code "64") (name "unconnected-(U5-D+-Pad18)") (class "Default")
      (node (ref "U5") (pin "18") (pinfunction "D+_18") (pintype "passive"))
    )
    (net (code "65") (name "unconnected-(U5-D--Pad7)") (class "Default")
      (node (ref "U5") (pin "7") (pinfunction "D-_7") (pintype "passive"))
    )
    (net (code "66") (name "unconnected-(U5-D--Pad19)") (class "Default")
      (node (ref "U5") (pin "19") (pinfunction "D-_19") (pintype "passive"))
    )
    (net (code "67") (name "unconnected-(U5-RX1+-Pad23)") (class "Default")
      (node (ref "U5") (pin "23") (pinfunction "RX1+_23") (pintype "passive"))
    )
    (net (code "68") (name "unconnected-(U5-RX1--Pad22)") (class "Default")
      (node (ref "U5") (pin "22") (pinfunction "RX1-_22") (pintype "passive"))
    )
    (net (code "69") (name "unconnected-(U5-RX2+-Pad11)") (class "Default")
      (node (ref "U5") (pin "11") (pinfunction "RX2+_11") (pintype "passive"))
    )
    (net (code "70") (name "unconnected-(U5-RX2--Pad10)") (class "Default")
      (node (ref "U5") (pin "10") (pinfunction "RX2-_10") (pintype "passive"))
    )
    (net (code "71") (name "unconnected-(U5-SBU1-Pad8)") (class "Default")
      (node (ref "U5") (pin "8") (pinfunction "SBU1_8") (pintype "passive"))
    )
    (net (code "72") (name "unconnected-(U5-SBU2-Pad20)") (class "Default")
      (node (ref "U5") (pin "20") (pinfunction "SBU2_20") (pintype "passive"))
    )
    (net (code "73") (name "unconnected-(U5-TX1+-Pad2)") (class "Default")
      (node (ref "U5") (pin "2") (pinfunction "TX1+_2") (pintype "passive"))
    )
    (net (code "74") (name "unconnected-(U5-TX1--Pad3)") (class "Default")
      (node (ref "U5") (pin "3") (pinfunction "TX1-_3") (pintype "passive"))
    )
    (net (code "75") (name "unconnected-(U5-TX2+-Pad14)") (class "Default")
      (node (ref "U5") (pin "14") (pinfunction "TX2+_14") (pintype "passive"))
    )
    (net (code "76") (name "unconnected-(U5-TX2--Pad15)") (class "Default")
      (node (ref "U5") (pin "15") (pinfunction "TX2-_15") (pintype "passive"))
    )
  )
)
